# Sensors.net
KiCad netlist of a schematic drawn in Altium Designer
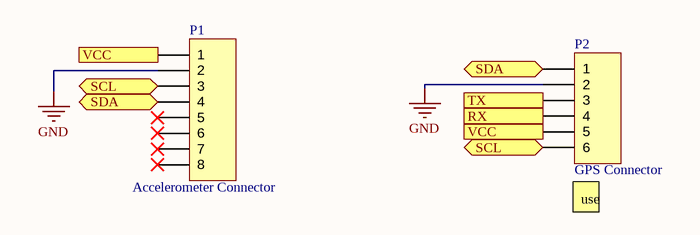
[diagram p0: Sensors.SchDoc]

(export (version "E")
  (design (tool "Eeschema 10.0.6"))
  (components
    (comp (ref "P1")
      (value "Accelerometer Connector")
      (footprint "HDR1X8")
      (description "Header, 8-Pin")
      (fields (field (name "PUBLISHER") "Altium Limited"))
      (libsource (lib "Miscellaneous Connectors") (part "Header 8"))
    )
    (comp (ref "P2")
      (value "GPS Connector")
      (footprint "HDR1X6")
      (description "Header, 6-Pin")
      (fields (field (name "PUBLISHER") "Altium Limited"))
      (libsource (lib "Miscellaneous Connectors") (part "Header 6"))
    )
  )
  (nets
    (net (code "1") (name "/RX") (class "Default")
      (node (ref "P2") (pin "4") (pinfunction "4_4") (pintype "passive"))
    )
    (net (code "2") (name "/SCL") (class "Default")
      (node (ref "P1") (pin "3") (pinfunction "3_3") (pintype "passive"))
      (node (ref "P2") (pin "6") (pinfunction "6_6") (pintype "passive"))
    )
    (net (code "3") (name "/SDA") (class "Default")
      (node (ref "P1") (pin "4") (pinfunction "4_4") (pintype "passive"))
      (node (ref "P2") (pin "1") (pinfunction "1_1") (pintype "passive"))
    )
    (net (code "4") (name "/TX") (class "Default")
      (node (ref "P2") (pin "3") (pinfunction "3_3") (pintype "passive"))
    )
    (net (code "5") (name "/VCC") (class "Default")
      (node (ref "P1") (pin "1") (pinfunction "1_1") (pintype "passive"))
      (node (ref "P2") (pin "5") (pinfunction "5_5") (pintype "passive"))
    )
    (net (code "6") (name "GND") (class "Default")
      (node (ref "P1") (pin "2") (pinfunction "2_2") (pintype "passive"))
      (node (ref "P2") (pin "2") (pinfunction "2_2") (pintype "passive"))
    )
    (net (code "7") (name "unconnected-(P1-Pad5)") (class "Default")
      (node (ref "P1") (pin "5") (pinfunction "5_5") (pintype "passive+no_connect"))
    )
    (net (code "8") (name "unconnected-(P1-Pad6)") (class "Default")
      (node (ref "P1") (pin "6") (pinfunction "6_6") (pintype "passive+no_connect"))
    )
    (net (code "9") (name "unconnected-(P1-Pad7)") (class "Default")
      (node (ref "P1") (pin "7") (pinfunction "7_7") (pintype "passive+no_connect"))
    )
    (net (code "10") (name "unconnected-(P1-Pad8)") (class "Default")
      (node (ref "P1") (pin "8") (pinfunction "8_8") (pintype "passive+no_connect"))
    )
  )
)
